# CAN.net
KiCad netlist of a schematic drawn in Altium Designer
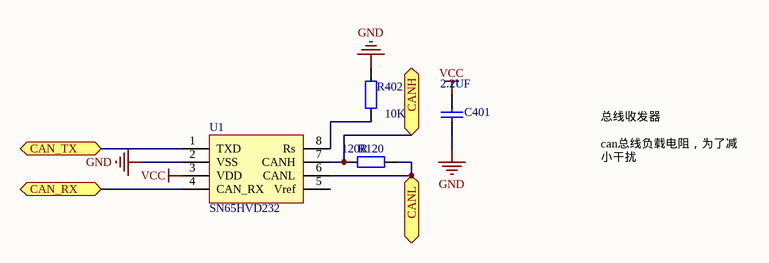
[diagram p0: CAN.SchDoc]

(export (version "E")
  (design (tool "Eeschema 10.0.6"))
  (components
    (comp (ref "C401")
      (value "2.2UF")
      (footprint "C-0603")
      (description "Capacitor")
      (fields (field (name "PUBLISHER") "Altium Limited"))
      (libsource (lib "TAOXUN") (part "CAP"))
    )
    (comp (ref "R120")
      (value "120R")
      (footprint "0603-2")
      (description "贴片电阻")
      (fields (field (name "PUBLISHER") "Altium Limited"))
      (libsource (lib "") (part "Res1_1"))
    )
    (comp (ref "R402")
      (value "10K")
      (footprint "0603-2")
      (description "贴片电阻")
      (fields (field (name "PUBLISHER") "Altium Limited"))
      (libsource (lib "TAOXUN") (part "Res1"))
    )
    (comp (ref "U1")
      (value "SN65HVD232")
      (footprint "SOIC8_N")
      (description "CAN收发器")
      (libsource (lib "TAOXUN") (part "AT24C02_1"))
    )
  )
  (nets
    (net (code "1") (name "/CANH") (class "Default")
      (node (ref "R120") (pin "2") (pinfunction "2_2") (pintype "passive"))
      (node (ref "U1") (pin "7") (pinfunction "CANH_7") (pintype "passive"))
    )
    (net (code "2") (name "/CANL") (class "Default")
      (node (ref "R120") (pin "1") (pinfunction "1_1") (pintype "passive"))
      (node (ref "U1") (pin "6") (pinfunction "CANL_6") (pintype "passive"))
    )
    (net (code "3") (name "/CAN_RX") (class "Default")
      (node (ref "U1") (pin "4") (pinfunction "CAN_RX_4") (pintype "passive"))
    )
    (net (code "4") (name "/CAN_TX") (class "Default")
      (node (ref "U1") (pin "1") (pinfunction "TXD_1") (pintype "passive"))
    )
    (net (code "5") (name "GND") (class "Default")
      (node (ref "C401") (pin "1") (pinfunction "1_1") (pintype "passive"))
      (node (ref "R402") (pin "2") (pinfunction "2_2") (pintype "passive"))
      (node (ref "U1") (pin "2") (pinfunction "VSS_2") (pintype "passive"))
    )
    (net (code "6") (name "Net-(U1-Rs)") (class "Default")
      (node (ref "R402") (pin "1") (pinfunction "1_1") (pintype "passive"))
      (node (ref "U1") (pin "8") (pinfunction "Rs_8") (pintype "passive"))
    )
    (net (code "7") (name "VCC") (class "Default")
      (node (ref "C401") (pin "2") (pinfunction "2_2") (pintype "passive"))
      (node (ref "U1") (pin "3") (pinfunction "VDD_3") (pintype "passive"))
    )
    (net (code "8") (name "unconnected-(U1-Vref-Pad5)") (class "Default")
      (node (ref "U1") (pin "5") (pinfunction "Vref_5") (pintype "passive"))
    )
  )
)
